# BTA-2way-2amp.net
KiCad netlist of a schematic drawn in EAGLE
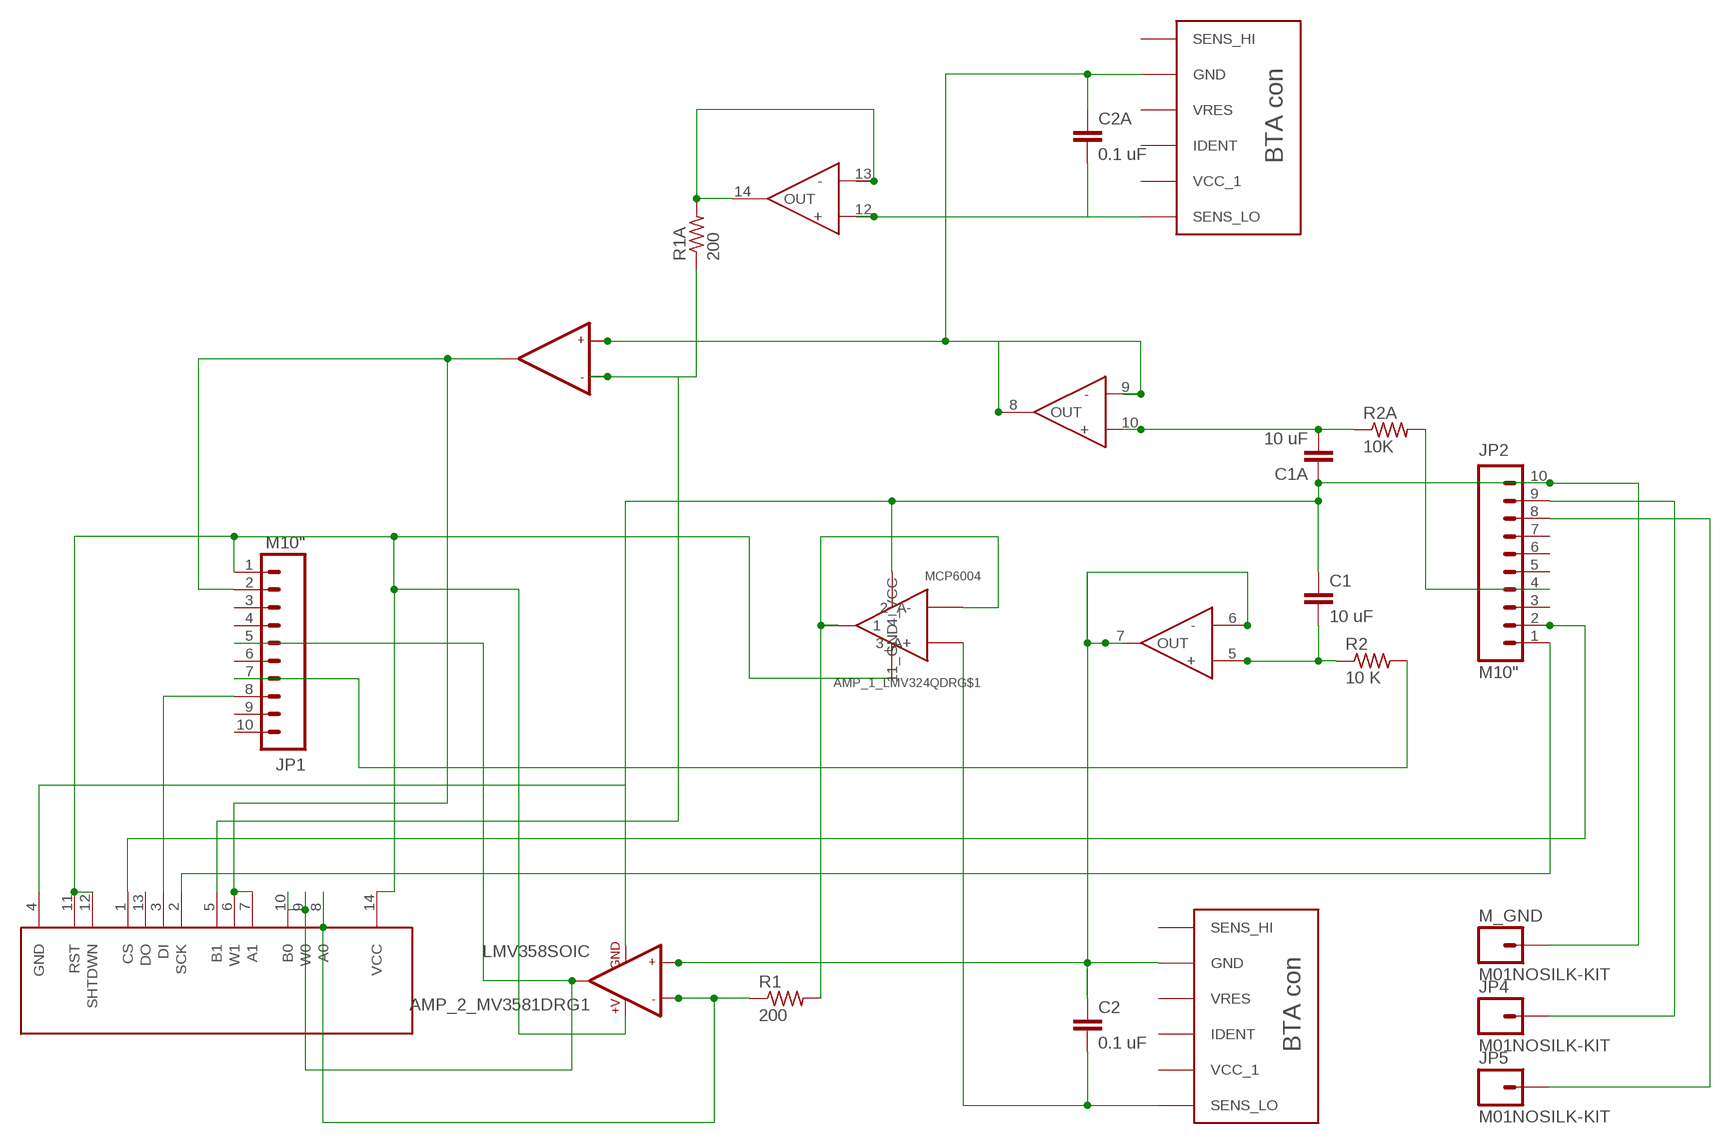
[diagram p0: schematic, sheet 1]

(export (version "E")
  (design (tool "Eeschema 10.0.6"))
  (components
    (comp (ref "AMP_1_LMV324QDR")
      (value "MCP6004")
      (footprint "eagle-import:SO014")
      (libsource (lib "eagle-import") (part "MCP6004"))
    )
    (comp (ref "AMP_2_MV3581DR")
      (value "LMV358SOIC")
      (footprint "eagle-import:SO08")
      (libsource (lib "eagle-import") (part "LMV358SOIC"))
    )
    (comp (ref "C1")
      (value "10 uF")
      (footprint "eagle-import:C1206")
      (libsource (lib "eagle-import") (part "C-EUC1206"))
    )
    (comp (ref "C1A")
      (value "10 uF")
      (footprint "eagle-import:C1206")
      (libsource (lib "eagle-import") (part "C-EUC1206"))
    )
    (comp (ref "C2")
      (value "0.1 uF")
      (footprint "eagle-import:C1206")
      (libsource (lib "eagle-import") (part "C-EUC1206"))
    )
    (comp (ref "C2A")
      (value "0.1 uF")
      (footprint "eagle-import:C1206")
      (libsource (lib "eagle-import") (part "C-EUC1206"))
    )
    (comp (ref "JP1")
      (value "M10\"")
      (footprint "eagle-import:1X10")
      (libsource (lib "eagle-import") (part "M10{dblquote}"))
    )
    (comp (ref "JP2")
      (value "M10\"")
      (footprint "eagle-import:1X10")
      (libsource (lib "eagle-import") (part "M10{dblquote}"))
    )
    (comp (ref "JP4")
      (value "M01NOSILK-KIT")
      (footprint "eagle-import:1X01NS-KIT")
      (libsource (lib "eagle-import") (part "M01NOSILK-KIT"))
    )
    (comp (ref "JP5")
      (value "M01NOSILK-KIT")
      (footprint "eagle-import:1X01NS-KIT")
      (libsource (lib "eagle-import") (part "M01NOSILK-KIT"))
    )
    (comp (ref "M_GND")
      (value "M01NOSILK-KIT")
      (footprint "eagle-import:1X01NS-KIT")
      (libsource (lib "eagle-import") (part "M01NOSILK-KIT"))
    )
    (comp (ref "POT-MCP4231")
      (value "MCP42XXX")
      (footprint "eagle-import:SO014")
      (libsource (lib "eagle-import") (part "MCP42XXX"))
    )
    (comp (ref "R1")
      (value "200")
      (footprint "eagle-import:R1206")
      (libsource (lib "eagle-import") (part "R-US_R1206"))
    )
    (comp (ref "R1A")
      (value "200")
      (footprint "eagle-import:R1206")
      (libsource (lib "eagle-import") (part "R-US_R1206"))
    )
    (comp (ref "R2")
      (value "10 K")
      (footprint "eagle-import:R1206")
      (libsource (lib "eagle-import") (part "R-US_R1206"))
    )
    (comp (ref "R2A")
      (value "10K")
      (footprint "eagle-import:R1206")
      (libsource (lib "eagle-import") (part "R-US_R1206"))
    )
    (comp (ref "U$1")
      (value "BTA_CON")
      (footprint "eagle-import:BTA_CON")
      (libsource (lib "eagle-import") (part "BTA_CON"))
    )
    (comp (ref "U$3")
      (value "BTA_CON")
      (footprint "eagle-import:BTA_CON")
      (libsource (lib "eagle-import") (part "BTA_CON"))
    )
  )
  (nets
    (net (code "1") (name "Net-(AMP_1_LMV324QDRA-2_A-)") (class "Default")
      (node (ref "AMP_1_LMV324QDR") (pin "1") (pinfunction "1_1") (pintype "bidirectional"))
      (node (ref "AMP_1_LMV324QDR") (pin "2") (pinfunction "2_A-_2") (pintype "bidirectional"))
      (node (ref "R1") (pin "2") (pinfunction "2_2") (pintype "passive"))
    )
    (net (code "2") (name "Net-(AMP_1_LMV324QDRA-3_A+)") (class "Default")
      (node (ref "AMP_1_LMV324QDR") (pin "3") (pinfunction "3_A+_3") (pintype "bidirectional"))
      (node (ref "C2") (pin "2") (pinfunction "2_2") (pintype "passive"))
      (node (ref "U$3") (pin "PIN_6") (pinfunction "SENS_LO_PIN_6") (pintype "bidirectional"))
    )
    (net (code "3") (name "Net-(AMP_1_LMV324QDRA-4_VCC)") (class "Default")
      (node (ref "AMP_1_LMV324QDR") (pin "4") (pinfunction "4_VCC_4") (pintype "power_in"))
      (node (ref "AMP_2_MV3581DR") (pin "8") (pinfunction "+V_8") (pintype "power_in"))
      (node (ref "JP1") (pin "1") (pinfunction "1_1") (pintype "passive"))
      (node (ref "POT-MCP4231") (pin "11") (pinfunction "RST_11") (pintype "bidirectional"))
      (node (ref "POT-MCP4231") (pin "12") (pinfunction "SHTDWN_12") (pintype "bidirectional"))
      (node (ref "POT-MCP4231") (pin "14") (pinfunction "VCC_14") (pintype "bidirectional"))
    )
    (net (code "4") (name "Net-(AMP_1_LMV324QDRA-11_GND)") (class "Default")
      (node (ref "AMP_1_LMV324QDR") (pin "11") (pinfunction "11_GND_11") (pintype "power_in"))
      (node (ref "AMP_2_MV3581DR") (pin "4") (pinfunction "GND_4") (pintype "power_in"))
      (node (ref "C1") (pin "1") (pinfunction "1_1") (pintype "passive"))
      (node (ref "C1A") (pin "1") (pinfunction "1_1") (pintype "passive"))
      (node (ref "JP2") (pin "10") (pinfunction "10_10") (pintype "passive"))
      (node (ref "M_GND") (pin "1") (pinfunction "1_1") (pintype "passive"))
      (node (ref "POT-MCP4231") (pin "4") (pinfunction "GND_4") (pintype "bidirectional"))
    )
    (net (code "5") (name "Net-(AMP_1_LMV324QDRB-+)") (class "Default")
      (node (ref "AMP_1_LMV324QDR") (pin "10") (pinfunction "+_10") (pintype "bidirectional"))
      (node (ref "C1A") (pin "2") (pinfunction "2_2") (pintype "passive"))
      (node (ref "R2A") (pin "1") (pinfunction "1_1") (pintype "passive"))
    )
    (net (code "6") (name "Net-(AMP_1_LMV324QDRB-OUT)") (class "Default")
      (node (ref "AMP_1_LMV324QDR") (pin "8") (pinfunction "OUT_8") (pintype "bidirectional"))
      (node (ref "AMP_2_MV3581DR") (pin "5") (pinfunction "+IN2_5") (pintype "input"))
      (node (ref "C2A") (pin "1") (pinfunction "1_1") (pintype "passive"))
      (node (ref "U$1") (pin "PIN_2") (pinfunction "GND_PIN_2") (pintype "bidirectional"))
    )
    (net (code "7") (name "Net-(AMP_1_LMV324QDRC-+)") (class "Default")
      (node (ref "AMP_1_LMV324QDR") (pin "12") (pinfunction "+_12") (pintype "bidirectional"))
      (node (ref "C2A") (pin "2") (pinfunction "2_2") (pintype "passive"))
      (node (ref "U$1") (pin "PIN_6") (pinfunction "SENS_LO_PIN_6") (pintype "bidirectional"))
    )
    (net (code "8") (name "Net-(AMP_1_LMV324QDRC--)") (class "Default")
      (node (ref "AMP_1_LMV324QDR") (pin "13") (pinfunction "-_13") (pintype "bidirectional"))
      (node (ref "AMP_1_LMV324QDR") (pin "14") (pinfunction "OUT_14") (pintype "bidirectional"))
      (node (ref "R1A") (pin "2") (pinfunction "2_2") (pintype "passive"))
    )
    (net (code "9") (name "Net-(AMP_1_LMV324QDRD-+)") (class "Default")
      (node (ref "AMP_1_LMV324QDR") (pin "5") (pinfunction "+_5") (pintype "bidirectional"))
      (node (ref "C1") (pin "2") (pinfunction "2_2") (pintype "passive"))
      (node (ref "R2") (pin "1") (pinfunction "1_1") (pintype "passive"))
    )
    (net (code "10") (name "Net-(AMP_1_LMV324QDRD--)") (class "Default")
      (node (ref "AMP_1_LMV324QDR") (pin "6") (pinfunction "-_6") (pintype "bidirectional"))
      (node (ref "AMP_1_LMV324QDR") (pin "7") (pinfunction "OUT_7") (pintype "bidirectional"))
      (node (ref "AMP_2_MV3581DR") (pin "3") (pinfunction "+IN1_3") (pintype "input"))
      (node (ref "C2") (pin "1") (pinfunction "1_1") (pintype "passive"))
      (node (ref "U$3") (pin "PIN_2") (pinfunction "GND_PIN_2") (pintype "bidirectional"))
    )
    (net (code "11") (name "Net-(AMP_2_MV3581DRA--IN1)") (class "Default")
      (node (ref "AMP_2_MV3581DR") (pin "2") (pinfunction "-IN1_2") (pintype "input"))
      (node (ref "POT-MCP4231") (pin "8") (pinfunction "A0_8") (pintype "bidirectional"))
      (node (ref "R1") (pin "1") (pinfunction "1_1") (pintype "passive"))
    )
    (net (code "12") (name "Net-(AMP_2_MV3581DRA-OUT1)") (class "Default")
      (node (ref "AMP_2_MV3581DR") (pin "1") (pinfunction "OUT1_1") (pintype "output"))
      (node (ref "JP1") (pin "5") (pinfunction "5_5") (pintype "passive"))
      (node (ref "POT-MCP4231") (pin "10") (pinfunction "B0_10") (pintype "bidirectional"))
      (node (ref "POT-MCP4231") (pin "9") (pinfunction "W0_9") (pintype "bidirectional"))
    )
    (net (code "13") (name "Net-(AMP_2_MV3581DRB--IN2)") (class "Default")
      (node (ref "AMP_2_MV3581DR") (pin "6") (pinfunction "-IN2_6") (pintype "input"))
      (node (ref "POT-MCP4231") (pin "5") (pinfunction "B1_5") (pintype "bidirectional"))
      (node (ref "R1A") (pin "1") (pinfunction "1_1") (pintype "passive"))
    )
    (net (code "14") (name "Net-(AMP_2_MV3581DRB-OUT2)") (class "Default")
      (node (ref "AMP_2_MV3581DR") (pin "7") (pinfunction "OUT2_7") (pintype "output"))
      (node (ref "JP1") (pin "2") (pinfunction "2_2") (pintype "passive"))
      (node (ref "POT-MCP4231") (pin "6") (pinfunction "W1_6") (pintype "bidirectional"))
      (node (ref "POT-MCP4231") (pin "7") (pinfunction "A1_7") (pintype "bidirectional"))
    )
    (net (code "15") (name "Net-(JP1-Pad7)") (class "Default")
      (node (ref "JP1") (pin "7") (pinfunction "7_7") (pintype "passive"))
      (node (ref "R2") (pin "2") (pinfunction "2_2") (pintype "passive"))
    )
    (net (code "16") (name "Net-(JP2-Pad4)") (class "Default")
      (node (ref "JP2") (pin "4") (pinfunction "4_4") (pintype "passive"))
      (node (ref "R2A") (pin "2") (pinfunction "2_2") (pintype "passive"))
    )
    (net (code "17") (name "Net-(JP2-Pad8)") (class "Default")
      (node (ref "JP2") (pin "8") (pinfunction "8_8") (pintype "passive"))
      (node (ref "JP5") (pin "1") (pinfunction "1_1") (pintype "passive"))
    )
    (net (code "18") (name "Net-(JP2-Pad9)") (class "Default")
      (node (ref "JP2") (pin "9") (pinfunction "9_9") (pintype "passive"))
      (node (ref "JP4") (pin "1") (pinfunction "1_1") (pintype "passive"))
    )
    (net (code "19") (name "Net-(POT-MCP4231-CS)") (class "Default")
      (node (ref "JP2") (pin "2") (pinfunction "2_2") (pintype "passive"))
      (node (ref "POT-MCP4231") (pin "1") (pinfunction "CS_1") (pintype "bidirectional"))
    )
    (net (code "20") (name "Net-(POT-MCP4231-DI)") (class "Default")
      (node (ref "JP1") (pin "8") (pinfunction "8_8") (pintype "passive"))
      (node (ref "POT-MCP4231") (pin "3") (pinfunction "DI_3") (pintype "bidirectional"))
    )
    (net (code "21") (name "Net-(POT-MCP4231-SCK)") (class "Default")
      (node (ref "JP2") (pin "1") (pinfunction "1_1") (pintype "passive"))
      (node (ref "POT-MCP4231") (pin "2") (pinfunction "SCK_2") (pintype "bidirectional"))
    )
    (net (code "22") (name "unconnected-(AMP_1_LMV324QDRB---Pad9)") (class "Default")
      (node (ref "AMP_1_LMV324QDR") (pin "9") (pinfunction "-_9") (pintype "bidirectional"))
    )
    (net (code "23") (name "unconnected-(JP1-Pad3)") (class "Default")
      (node (ref "JP1") (pin "3") (pinfunction "3_3") (pintype "passive"))
    )
    (net (code "24") (name "unconnected-(JP1-Pad4)") (class "Default")
      (node (ref "JP1") (pin "4") (pinfunction "4_4") (pintype "passive"))
    )
    (net (code "25") (name "unconnected-(JP1-Pad6)") (class "Default")
      (node (ref "JP1") (pin "6") (pinfunction "6_6") (pintype "passive"))
    )
    (net (code "26") (name "unconnected-(JP1-Pad9)") (class "Default")
      (node (ref "JP1") (pin "9") (pinfunction "9_9") (pintype "passive"))
    )
    (net (code "27") (name "unconnected-(JP1-Pad10)") (class "Default")
      (node (ref "JP1") (pin "10") (pinfunction "10_10") (pintype "passive"))
    )
    (net (code "28") (name "unconnected-(JP2-Pad3)") (class "Default")
      (node (ref "JP2") (pin "3") (pinfunction "3_3") (pintype "passive"))
    )
    (net (code "29") (name "unconnected-(JP2-Pad5)") (class "Default")
      (node (ref "JP2") (pin "5") (pinfunction "5_5") (pintype "passive"))
    )
    (net (code "30") (name "unconnected-(JP2-Pad6)") (class "Default")
      (node (ref "JP2") (pin "6") (pinfunction "6_6") (pintype "passive"))
    )
    (net (code "31") (name "unconnected-(JP2-Pad7)") (class "Default")
      (node (ref "JP2") (pin "7") (pinfunction "7_7") (pintype "passive"))
    )
    (net (code "32") (name "unconnected-(POT-MCP4231-DO-Pad13)") (class "Default")
      (node (ref "POT-MCP4231") (pin "13") (pinfunction "DO_13") (pintype "bidirectional"))
    )
    (net (code "33") (name "unconnected-(U$1-IDENT-PadPIN_4)") (class "Default")
      (node (ref "U$1") (pin "PIN_4") (pinfunction "IDENT_PIN_4") (pintype "bidirectional"))
    )
    (net (code "34") (name "unconnected-(U$1-SENS_HI-PadPIN_1)") (class "Default")
      (node (ref "U$1") (pin "PIN_1") (pinfunction "SENS_HI_PIN_1") (pintype "bidirectional"))
    )
    (net (code "35") (name "unconnected-(U$1-VCC_1-PadPIN_5)") (class "Default")
      (node (ref "U$1") (pin "PIN_5") (pinfunction "VCC_1_PIN_5") (pintype "bidirectional"))
    )
    (net (code "36") (name "unconnected-(U$1-VRES-PadPIN_3)") (class "Default")
      (node (ref "U$1") (pin "PIN_3") (pinfunction "VRES_PIN_3") (pintype "bidirectional"))
    )
    (net (code "37") (name "unconnected-(U$3-IDENT-PadPIN_4)") (class "Default")
      (node (ref "U$3") (pin "PIN_4") (pinfunction "IDENT_PIN_4") (pintype "bidirectional"))
    )
    (net (code "38") (name "unconnected-(U$3-SENS_HI-PadPIN_1)") (class "Default")
      (node (ref "U$3") (pin "PIN_1") (pinfunction "SENS_HI_PIN_1") (pintype "bidirectional"))
    )
    (net (code "39") (name "unconnected-(U$3-VCC_1-PadPIN_5)") (class "Default")
      (node (ref "U$3") (pin "PIN_5") (pinfunction "VCC_1_PIN_5") (pintype "bidirectional"))
    )
    (net (code "40") (name "unconnected-(U$3-VRES-PadPIN_3)") (class "Default")
      (node (ref "U$3") (pin "PIN_3") (pinfunction "VRES_PIN_3") (pintype "bidirectional"))
    )
  )
)
